# 3_Voltage_Converters.net
KiCad netlist of a schematic drawn in Altium Designer
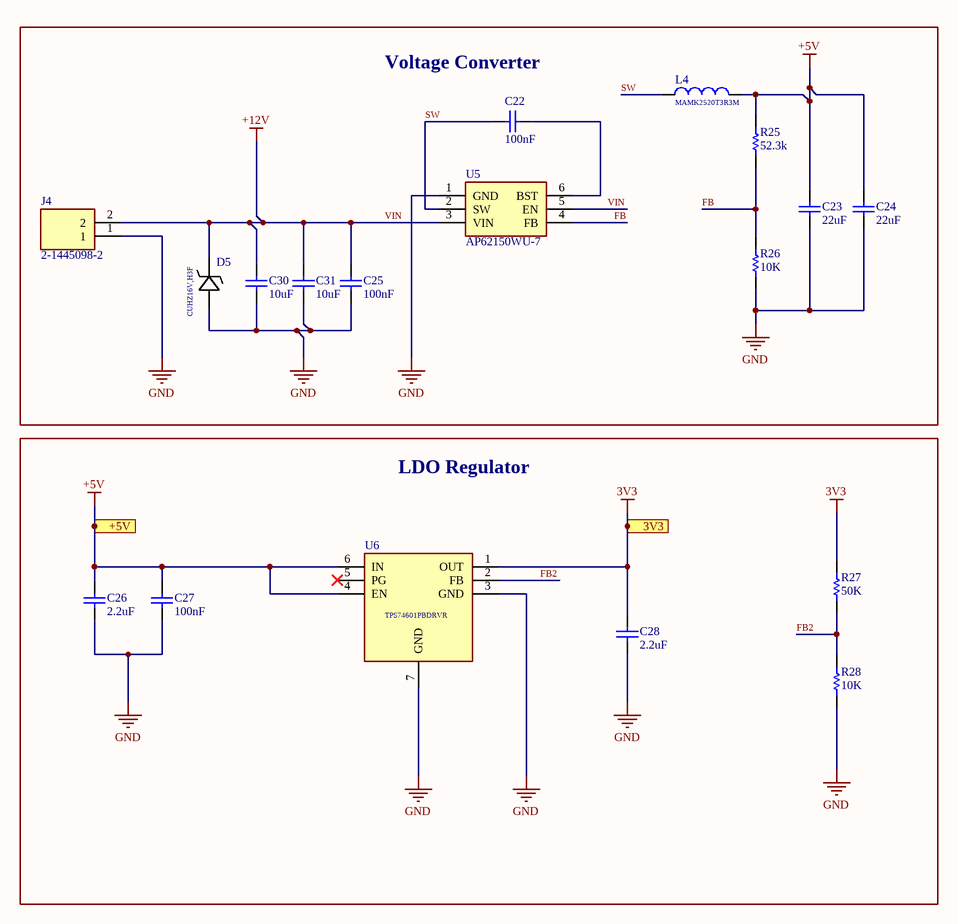
[diagram p0: [3] Voltage Converters.SchDoc]

(export (version "E")
  (design (tool "Eeschema 10.0.6"))
  (components
    (comp (ref "C22")
      (value "100nF")
      (footprint "Capacitor 0402")
      (description "Capacitor Ceramico SMD 0402")
      (libsource (lib "Mi Libreria") (part "Capacitor 0402"))
    )
    (comp (ref "C23")
      (value "22uF")
      (footprint "CAPACITOR 0805")
      (description "Capacitor Cerámico SMD 0805")
      (libsource (lib "Mi Libreria") (part "Capacitor 0805"))
    )
    (comp (ref "C24")
      (value "22uF")
      (footprint "CAPACITOR 0805")
      (description "Capacitor Cerámico SMD 0805")
      (libsource (lib "Mi Libreria") (part "Capacitor 0805"))
    )
    (comp (ref "C25")
      (value "100nF")
      (footprint "Capacitor 0402")
      (description "Capacitor Ceramico SMD 0402")
      (libsource (lib "Mi Libreria") (part "Capacitor 0402"))
    )
    (comp (ref "C26")
      (value "2.2uF")
      (footprint "CAPACITOR 0805")
      (description "Capacitor Cerámico SMD 0805")
      (libsource (lib "Mi Libreria") (part "Capacitor 0805"))
    )
    (comp (ref "C27")
      (value "100nF")
      (footprint "Capacitor 0402")
      (description "Capacitor Ceramico SMD 0402")
      (libsource (lib "Mi Libreria") (part "Capacitor 0402"))
    )
    (comp (ref "C28")
      (value "2.2uF")
      (footprint "CAPACITOR 0805")
      (description "Capacitor Cerámico SMD 0805")
      (libsource (lib "Mi Libreria") (part "Capacitor 0805"))
    )
    (comp (ref "C30")
      (value "10uF")
      (footprint "CAPACITOR 0805")
      (description "Capacitor Cerámico SMD 0805")
      (libsource (lib "Mi Libreria") (part "Capacitor 0805"))
    )
    (comp (ref "C31")
      (value "10uF")
      (footprint "CAPACITOR 0805")
      (description "Capacitor Cerámico SMD 0805")
      (libsource (lib "Mi Libreria") (part "Capacitor 0805"))
    )
    (comp (ref "D5")
      (value "CUHZ16V,H3F")
      (footprint "SOD-323HEUS2H_TOS")
      (description "16 V TVS Diode, SOD-323HE(US2H)")
      (fields (field (name "COPYRIGHT") "Copyright (C) 2025 Ultra Librarian. All rights reserved."))
      (libsource (lib "CUHZ16V,H3F") (part "CUHZ16V,H3F"))
    )
    (comp (ref "J4")
      (value "2-1445098-2")
      (footprint "214450982")
      (description "Configuration Features: Number of Rows 1")
      (fields (field (name "MOUSER PART NUMBER") "571-2-1445098-2"))
      (libsource (lib "2-1445098-2") (part "2-1445098-2"))
    )
    (comp (ref "L4")
      (value "MAMK2520T3R3M")
      (footprint "INDC2520X120N")
      (description "3.3 ÂµH Shielded Drum Core, Wirewound Inductor 1.7 A 156mOhm Max 1008 (2520 Metric)")
      (fields (field (name "MF") "Taiyo Yuden"))
      (libsource (lib "MAMK2520T3R3M") (part "MAMK2520T3R3M"))
    )
    (comp (ref "R25")
      (value "52.3k")
      (footprint "Resistencia 0402")
      (description "Resistencia SMD 0402")
      (libsource (lib "Mi Libreria") (part "Resistencia SMD 0402"))
    )
    (comp (ref "R26")
      (value "10K")
      (footprint "Resistencia 0402")
      (description "Resistencia SMD 0402")
      (libsource (lib "Mi Libreria") (part "Resistencia SMD 0402"))
    )
    (comp (ref "R27")
      (value "50K")
      (footprint "Resistencia 0402")
      (description "Resistencia SMD 0402")
      (libsource (lib "Mi Libreria") (part "Resistencia SMD 0402"))
    )
    (comp (ref "R28")
      (value "10K")
      (footprint "Resistencia 0402")
      (description "Resistencia SMD 0402")
      (libsource (lib "Mi Libreria") (part "Resistencia SMD 0402"))
    )
    (comp (ref "U5")
      (value "AP62150WU-7")
      (footprint "SOT95P280X100-6N")
      (description "Switching Voltage Regulators DCDC Conv HV Buck TSOT26 T&R 3K")
      (fields (field (name "MOUSER PART NUMBER") "621-AP62150WU-7"))
      (libsource (lib "AP62150WU-7") (part "AP62150WU-7"))
    )
    (comp (ref "U6")
      (value "TPS74601PBDRVR")
      (footprint "SON65P200X200X80-7N")
      (description "Adjustable 1-A low-dropout (LDO) linear regulator with power good")
      (fields (field (name "MOUSER PART NUMBER") "595-TPS74601PBDRVR"))
      (libsource (lib "TPS74601PBDRVR") (part "TPS74601PBDRVR"))
    )
  )
  (nets
    (net (code "1") (name "+5V") (class "Default")
      (node (ref "C23") (pin "2") (pinfunction "2_2") (pintype "passive"))
      (node (ref "C24") (pin "2") (pinfunction "2_2") (pintype "passive"))
      (node (ref "C26") (pin "2") (pinfunction "2_2") (pintype "passive"))
      (node (ref "C27") (pin "2") (pinfunction "2_2") (pintype "passive"))
      (node (ref "L4") (pin "2") (pinfunction "2_2") (pintype "passive"))
      (node (ref "R25") (pin "2") (pinfunction "B_2") (pintype "passive"))
      (node (ref "U6") (pin "4") (pinfunction "EN_4") (pintype "passive"))
      (node (ref "U6") (pin "6") (pinfunction "IN_6") (pintype "passive"))
    )
    (net (code "2") (name "+12V") (class "Default")
      (node (ref "C25") (pin "2") (pinfunction "2_2") (pintype "passive"))
      (node (ref "C30") (pin "2") (pinfunction "2_2") (pintype "passive"))
      (node (ref "C31") (pin "2") (pinfunction "2_2") (pintype "passive"))
      (node (ref "D5") (pin "1") (pinfunction "CATHODE_1") (pintype "passive"))
      (node (ref "J4") (pin "2") (pinfunction "2_2") (pintype "passive"))
      (node (ref "U5") (pin "3") (pinfunction "VIN_3") (pintype "passive"))
      (node (ref "U5") (pin "5") (pinfunction "EN_5") (pintype "passive"))
    )
    (net (code "3") (name "/FB") (class "Default")
      (node (ref "R25") (pin "1") (pinfunction "A_1") (pintype "passive"))
      (node (ref "R26") (pin "2") (pinfunction "B_2") (pintype "passive"))
      (node (ref "U5") (pin "4") (pinfunction "FB_4") (pintype "passive"))
    )
    (net (code "4") (name "/FB2") (class "Default")
      (node (ref "R27") (pin "1") (pinfunction "A_1") (pintype "passive"))
      (node (ref "R28") (pin "2") (pinfunction "B_2") (pintype "passive"))
      (node (ref "U6") (pin "2") (pinfunction "FB_2") (pintype "passive"))
    )
    (net (code "5") (name "/SW") (class "Default")
      (node (ref "C22") (pin "2") (pinfunction "2_2") (pintype "passive"))
      (node (ref "L4") (pin "1") (pinfunction "1_1") (pintype "passive"))
      (node (ref "U5") (pin "2") (pinfunction "SW_2") (pintype "passive"))
    )
    (net (code "6") (name "3V3") (class "Default")
      (node (ref "C28") (pin "2") (pinfunction "2_2") (pintype "passive"))
      (node (ref "R27") (pin "2") (pinfunction "B_2") (pintype "passive"))
      (node (ref "U6") (pin "1") (pinfunction "OUT_1") (pintype "passive"))
    )
    (net (code "7") (name "GND") (class "Default")
      (node (ref "C23") (pin "1") (pinfunction "1_1") (pintype "passive"))
      (node (ref "C24") (pin "1") (pinfunction "1_1") (pintype "passive"))
      (node (ref "C25") (pin "1") (pinfunction "1_1") (pintype "passive"))
      (node (ref "C26") (pin "1") (pinfunction "1_1") (pintype "passive"))
      (node (ref "C27") (pin "1") (pinfunction "1_1") (pintype "passive"))
      (node (ref "C28") (pin "1") (pinfunction "1_1") (pintype "passive"))
      (node (ref "C30") (pin "1") (pinfunction "1_1") (pintype "passive"))
      (node (ref "C31") (pin "1") (pinfunction "1_1") (pintype "passive"))
      (node (ref "D5") (pin "2") (pinfunction "ANODE_2") (pintype "passive"))
      (node (ref "J4") (pin "1") (pinfunction "1_1") (pintype "passive"))
      (node (ref "R26") (pin "1") (pinfunction "A_1") (pintype "passive"))
      (node (ref "R28") (pin "1") (pinfunction "A_1") (pintype "passive"))
      (node (ref "U5") (pin "1") (pinfunction "GND_1") (pintype "passive"))
      (node (ref "U6") (pin "3") (pinfunction "GND_3") (pintype "passive"))
      (node (ref "U6") (pin "7") (pinfunction "GND_7") (pintype "passive"))
    )
    (net (code "8") (name "Net-(U5-BST)") (class "Default")
      (node (ref "C22") (pin "1") (pinfunction "1_1") (pintype "passive"))
      (node (ref "U5") (pin "6") (pinfunction "BST_6") (pintype "passive"))
    )
    (net (code "9") (name "unconnected-(U6-PG-Pad5)") (class "Default")
      (node (ref "U6") (pin "5") (pinfunction "PG_5") (pintype "passive+no_connect"))
    )
  )
)
